# sensor.net
KiCad netlist of a schematic drawn in EAGLE
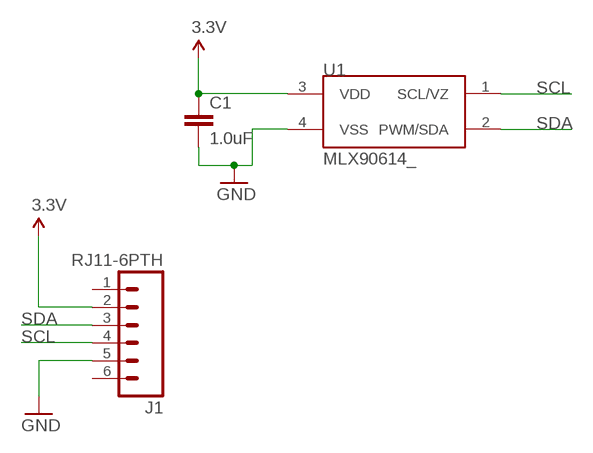
[diagram p0: schematic, sheet 1]

(export (version "E")
  (design (tool "Eeschema 10.0.6"))
  (components
    (comp (ref "C1")
      (value "1.0uF")
      (footprint "eagle-import:0805")
      (libsource (lib "eagle-import") (part "1.0UF-25V-+80/-20(0805)"))
    )
    (comp (ref "J1")
      (value "RJ11-6PTH")
      (footprint "eagle-import:RJ11-6")
      (libsource (lib "eagle-import") (part "RJ11-6PTH"))
    )
    (comp (ref "U1")
      (value "MLX90614_")
      (footprint "eagle-import:TO-39")
      (libsource (lib "eagle-import") (part "MLX90614_"))
    )
  )
  (nets
    (net (code "1") (name "/SCL") (class "Default")
      (node (ref "J1") (pin "4") (pinfunction "4_4") (pintype "passive"))
      (node (ref "U1") (pin "1") (pinfunction "SCL/VZ_1") (pintype "bidirectional"))
    )
    (net (code "2") (name "/SDA") (class "Default")
      (node (ref "J1") (pin "3") (pinfunction "3_3") (pintype "passive"))
      (node (ref "U1") (pin "2") (pinfunction "PWM/SDA_2") (pintype "bidirectional"))
    )
    (net (code "3") (name "3.3V") (class "Default")
      (node (ref "C1") (pin "1") (pinfunction "1_1") (pintype "passive"))
      (node (ref "J1") (pin "2") (pinfunction "2_2") (pintype "passive"))
      (node (ref "U1") (pin "3") (pinfunction "VDD_3") (pintype "bidirectional"))
    )
    (net (code "4") (name "GND") (class "Default")
      (node (ref "C1") (pin "2") (pinfunction "2_2") (pintype "passive"))
      (node (ref "J1") (pin "5") (pinfunction "5_5") (pintype "passive"))
      (node (ref "U1") (pin "4") (pinfunction "VSS_4") (pintype "bidirectional"))
    )
    (net (code "5") (name "unconnected-(J1-Pad1)") (class "Default")
      (node (ref "J1") (pin "1") (pinfunction "1_1") (pintype "passive"))
    )
    (net (code "6") (name "unconnected-(J1-Pad6)") (class "Default")
      (node (ref "J1") (pin "6") (pinfunction "6_6") (pintype "passive"))
    )
  )
)
